# Shuttler_AMC.net
KiCad netlist of a schematic drawn in Altium Designer
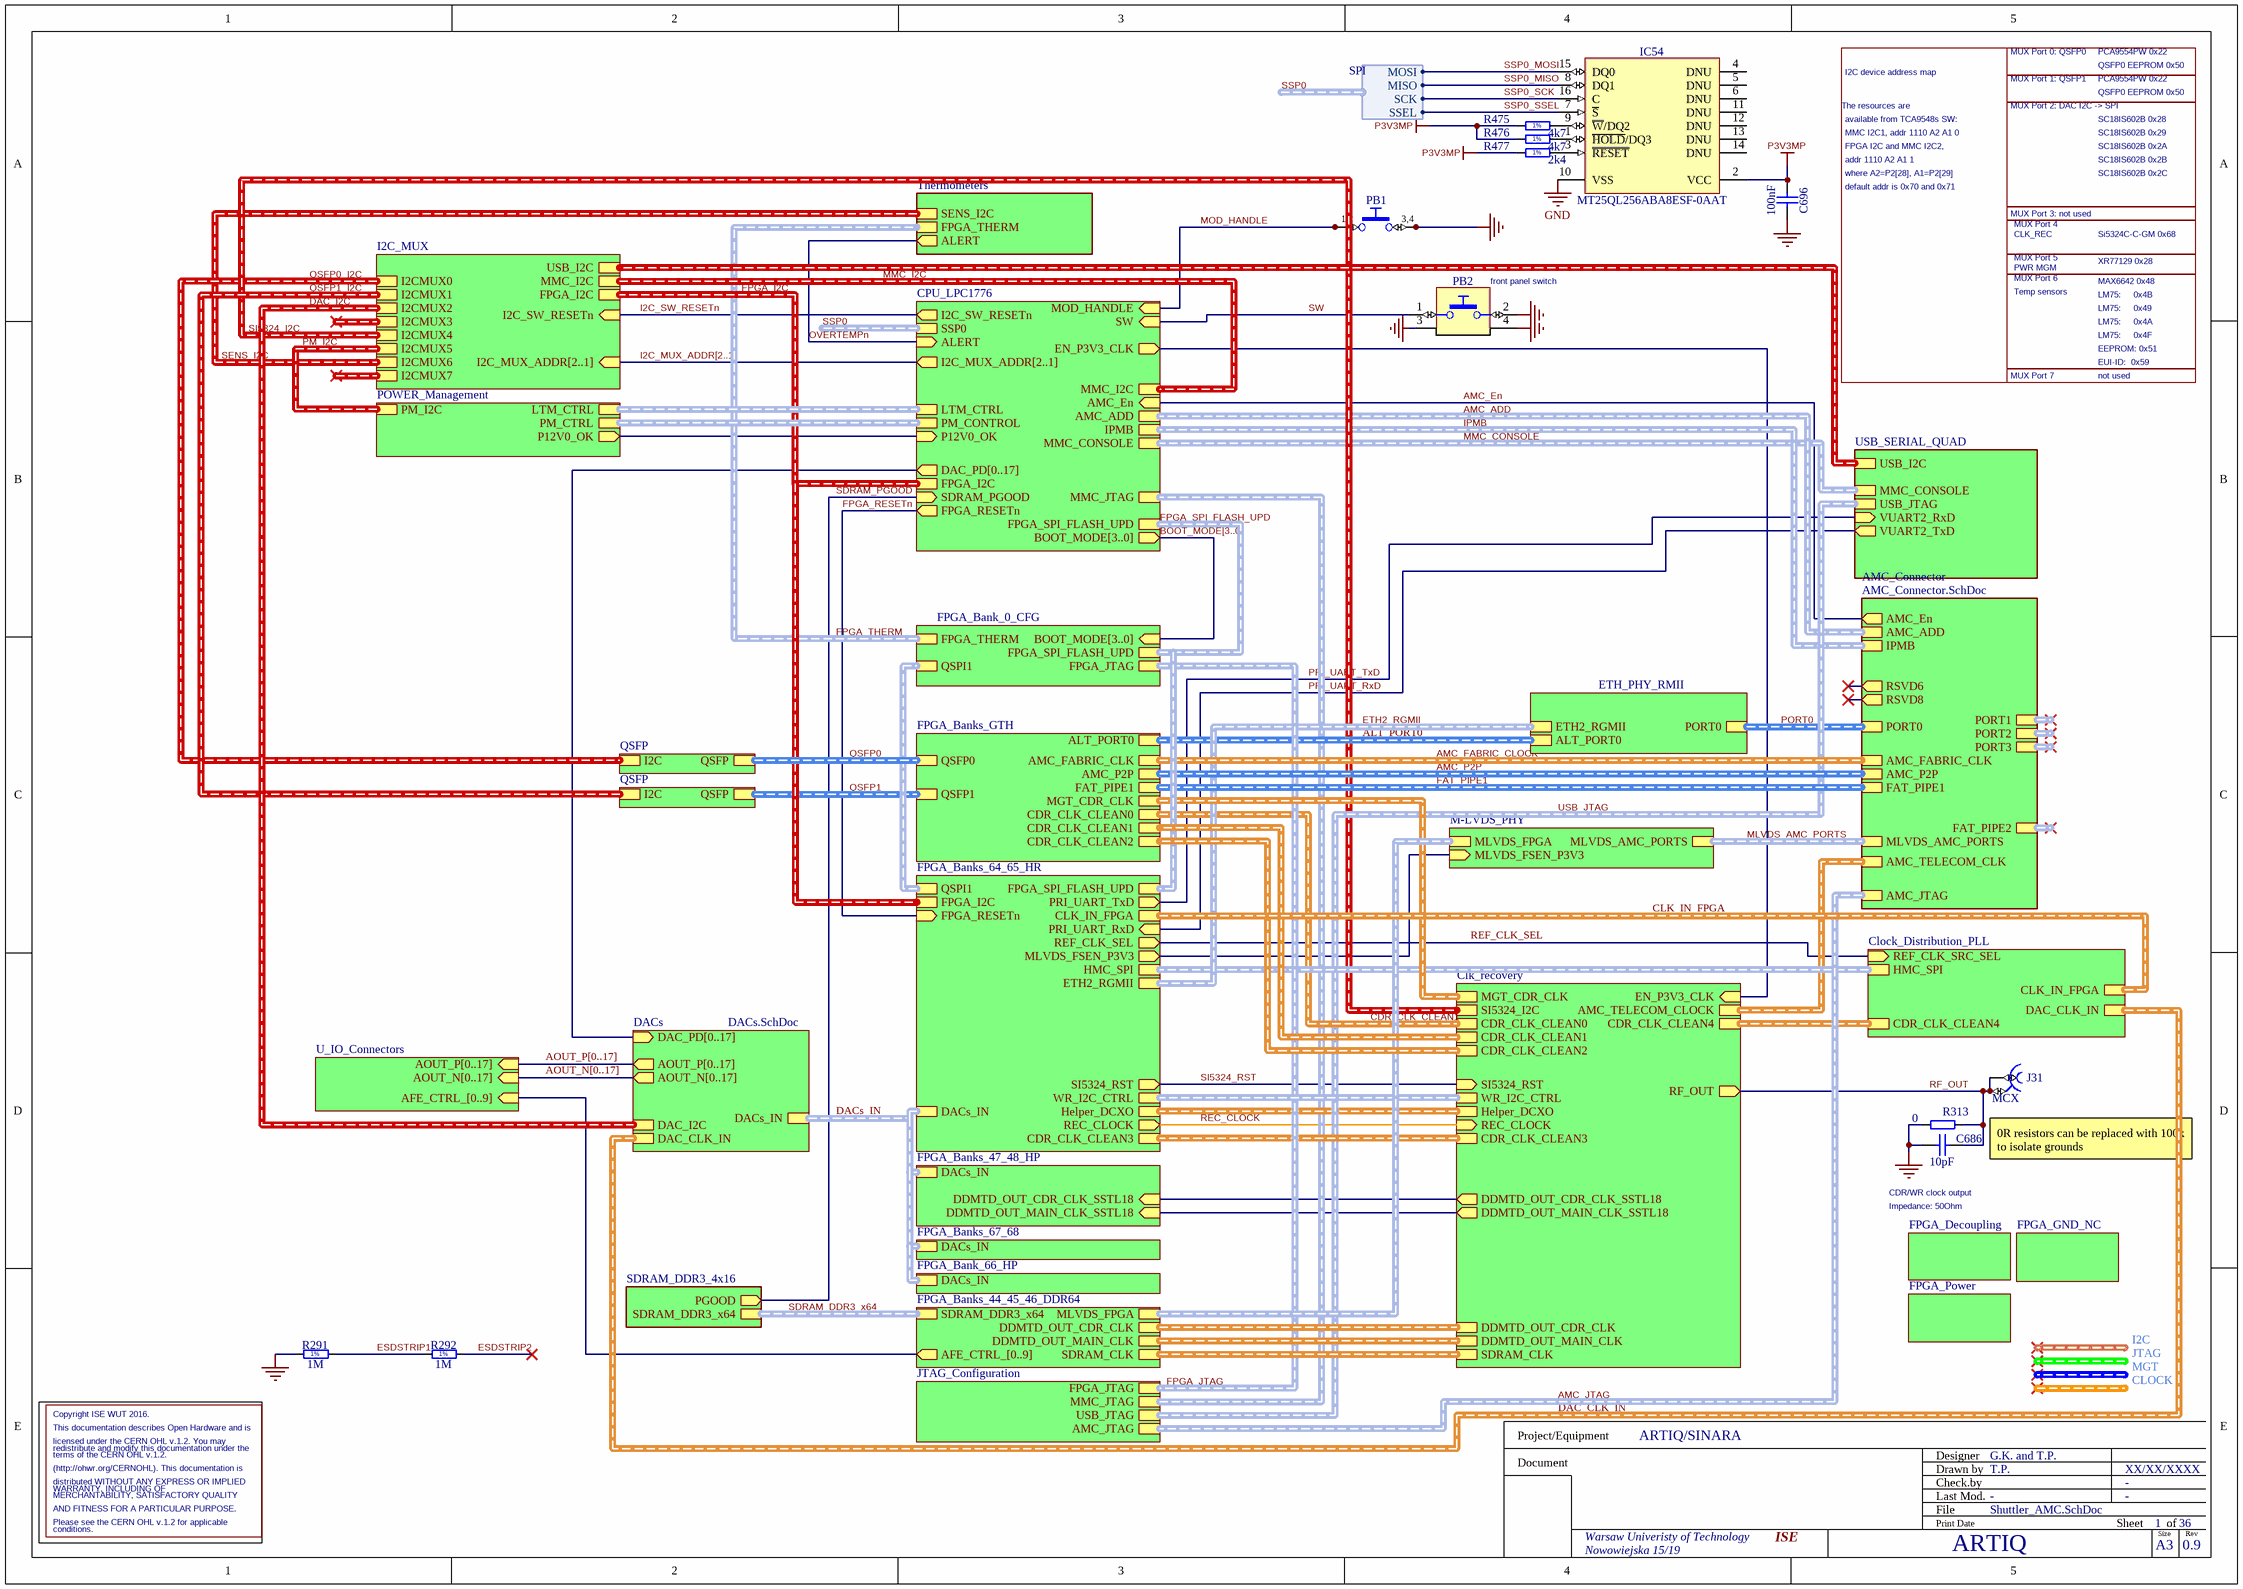
[diagram p0: Shuttler_AMC.SchDoc]

(export (version "E")
  (design (tool "Eeschema 10.0.6"))
  (components
    (comp (ref "C686")
      (value "10pF")
      (footprint "CAPC1608X87N")
      (description "Non-polarised capacitor")
      (fields
        (field (name "MANUFACTURER PART NUMBER") "CC0603_10PF_50V_5%_NP0")
        (field (name "MANUFACTURER") "GENERIC")
        (field (name "AUTHOR") "CERN DEM JLC")
      )
      (libsource (lib "Capacitors") (part "Capacitor - non polarized"))
    )
    (comp (ref "C696")
      (value "100nF")
      (footprint "CAPC0603X33N")
      (description "Non-polarised capacitor")
      (fields
        (field (name "MANUFACTURER PART NUMBER") "CC0201_100NF_6.3V_10%_X5R")
        (field (name "MANUFACTURER") "GENERIC")
        (field (name "AUTHOR") "CERN DEM JLC")
      )
      (libsource (lib "Capacitors") (part "Capacitor - non polarized"))
    )
    (comp (ref "IC54")
      (value "MT25QL256ABA8ESF-0AAT")
      (footprint "SOIC127P1030X265-16N")
      (description "256Mbit (32MB), 2.7V-3.6V, Multiple I/O Serial NOR Flash Memory,with Reset# & Hold#")
      (fields (field (name "MANUFACTURER") "MICRON TECHNOLOGY") (field (name "AUTHOR") "CERN DEM JLC"))
      (libsource (lib "ICs And Semiconductors") (part "MT25QL256ABA8ESF"))
    )
    (comp (ref "J31")
      (value "MCX")
      (footprint "AMPHENOL_ARF2521-ND")
      (fields
        (field (name "PART NUMBER") "AMPHENOL_ARF2521-ND")
        (field (name "MANUFACTURER") "AMPHENOL")
        (field (name "AUTHOR") "GK")
      )
      (libsource (lib "LIBRARY_SCH") (part "CON_MCX"))
    )
    (comp (ref "PB1")
      (value "Push Button")
      (footprint "SW_C&K_HDT0001")
      (description "Push-Button Switch SPDT")
      (fields
        (field (name "MANUFACTURER PART NUMBER") "HDT0001")
        (field (name "MANUFACTURER") "C&K")
        (field (name "AUTHOR") "CERN DEM JLC")
      )
      (libsource (lib "Eletro-mechanical") (part "PB SPST 12NO-34NO"))
    )
    (comp (ref "PB2")
      (value "Push Button")
      (footprint "PB_ALPS_SKHHLQA010")
      (description "Push-Button Switch SPDT")
      (fields
        (field (name "MANUFACTURER PART NUMBER") "SKHHLQA010")
        (field (name "MANUFACTURER") "ALPS")
        (field (name "AUTHOR") "CERN DEM JLC")
      )
      (libsource (lib "Eletro-mechanical") (part "PB SPST 1NO-2NO 34CASE"))
    )
    (comp (ref "R291")
      (value "1M")
      (footprint "RESC5025X65N")
      (description "Resistor - 1%")
      (fields
        (field (name "MANUFACTURER PART NUMBER") "R2010_1M_1%_0.5W_200PPM")
        (field (name "MANUFACTURER") "GENERIC")
        (field (name "AUTHOR") "CERN DEM JLC")
      )
      (libsource (lib "Resistors") (part "Resistor - 1%"))
    )
    (comp (ref "R292")
      (value "1M")
      (footprint "RESC5025X65N")
      (description "Resistor - 1%")
      (fields
        (field (name "MANUFACTURER PART NUMBER") "R2010_1M_1%_0.5W_200PPM")
        (field (name "MANUFACTURER") "GENERIC")
        (field (name "AUTHOR") "CERN DEM JLC")
      )
      (libsource (lib "Resistors") (part "Resistor - 1%"))
    )
    (comp (ref "R313")
      (value "0")
      (footprint "RESC1005X40N")
      (description "Resistor")
      (fields
        (field (name "MANUFACTURER PART NUMBER") "R0402_0R_JUMPER")
        (field (name "MANUFACTURER") "GENERIC")
        (field (name "AUTHOR") "CERN DEM JLC")
      )
      (libsource (lib "Resistors") (part "Resistor"))
    )
    (comp (ref "R475")
      (value "4k7")
      (footprint "RESC1005X40N")
      (description "Resistor - 1%")
      (fields
        (field (name "MANUFACTURER PART NUMBER") "R0402_4K7_1%_0.0625W_100PPM")
        (field (name "MANUFACTURER") "GENERIC")
        (field (name "AUTHOR") "CERN DEM JLC")
      )
      (libsource (lib "Resistors") (part "Resistor - 1%"))
    )
    (comp (ref "R476")
      (value "4k7")
      (footprint "RESC1005X40N")
      (description "Resistor - 1%")
      (fields
        (field (name "MANUFACTURER PART NUMBER") "R0402_4K7_1%_0.0625W_100PPM")
        (field (name "MANUFACTURER") "GENERIC")
        (field (name "AUTHOR") "CERN DEM JLC")
      )
      (libsource (lib "Resistors") (part "Resistor - 1%"))
    )
    (comp (ref "R477")
      (value "2k4")
      (footprint "RESC1005X40N")
      (description "Resistor - 1%")
      (fields
        (field (name "PART NUMBER") "R0402_2K4_1%_0.0625W_100PPM")
        (field (name "POWER") "0.0625W")
        (field (name "AUTHOR") "CERN DEM JLC")
      )
      (libsource (lib "Resistors") (part "Resistor - 1%"))
    )
  )
  (nets
    (net (code "91") (name "/ESDSTRIP1") (class "Default")
      (node (ref "R291") (pin "2") (pinfunction "2_2") (pintype "passive"))
      (node (ref "R292") (pin "1") (pinfunction "1_1") (pintype "passive"))
    )
    (net (code "92") (name "/ESDSTRIP2") (class "Default")
      (node (ref "R292") (pin "2") (pinfunction "2_2") (pintype "passive+no_connect"))
    )
    (net (code "106") (name "/MOD_HANDLE") (class "Default")
      (node (ref "PB1") (pin "1") (pinfunction "1_1") (pintype "bidirectional"))
      (node (ref "PB1") (pin "2") (pinfunction "2_2") (pintype "bidirectional"))
    )
    (net (code "118") (name "/RF_OUT") (class "Default")
      (node (ref "C686") (pin "2") (pinfunction "2_2") (pintype "passive"))
      (node (ref "J31") (pin "1") (pinfunction "1_1") (pintype "bidirectional"))
      (node (ref "J31") (pin "2") (pinfunction "2_2") (pintype "bidirectional"))
      (node (ref "R313") (pin "1") (pinfunction "1_1") (pintype "passive"))
    )
    (net (code "124") (name "/SSP0_MISO") (class "Default")
      (node (ref "IC54") (pin "8") (pinfunction "DQ1_8") (pintype "bidirectional"))
    )
    (net (code "125") (name "/SSP0_MOSI") (class "Default")
      (node (ref "IC54") (pin "15") (pinfunction "DQ0_15") (pintype "bidirectional"))
    )
    (net (code "126") (name "/SSP0_SCK") (class "Default")
      (node (ref "IC54") (pin "16") (pinfunction "C_16") (pintype "input"))
    )
    (net (code "127") (name "/SSP0_SSEL") (class "Default")
      (node (ref "IC54") (pin "7") (pinfunction "~{S}_7") (pintype "input"))
    )
    (net (code "129") (name "/SW") (class "Default")
      (node (ref "PB2") (pin "1") (pinfunction "1_1") (pintype "bidirectional"))
    )
    (net (code "163") (name "GND") (class "Default")
      (node (ref "C686") (pin "1") (pinfunction "1_1") (pintype "passive"))
      (node (ref "C696") (pin "1") (pinfunction "1_1") (pintype "passive"))
      (node (ref "IC54") (pin "10") (pinfunction "VSS_10") (pintype "power_in"))
      (node (ref "PB1") (pin "3") (pinfunction "3_3") (pintype "bidirectional"))
      (node (ref "PB1") (pin "4") (pinfunction "4_4") (pintype "bidirectional"))
      (node (ref "PB2") (pin "2") (pinfunction "2_2") (pintype "bidirectional"))
      (node (ref "PB2") (pin "3") (pinfunction "3_3") (pintype "passive"))
      (node (ref "PB2") (pin "4") (pinfunction "4_4") (pintype "passive"))
      (node (ref "R291") (pin "1") (pinfunction "1_1") (pintype "passive"))
      (node (ref "R313") (pin "2") (pinfunction "2_2") (pintype "passive"))
    )
    (net (code "164") (name "Net-(IC54-~{HOLD}{slash}DQ3)") (class "Default")
      (node (ref "IC54") (pin "1") (pinfunction "~{HOLD}/DQ3_1") (pintype "bidirectional"))
      (node (ref "R476") (pin "2") (pinfunction "2_2") (pintype "passive"))
    )
    (net (code "165") (name "Net-(IC54-~{RESET})") (class "Default")
      (node (ref "IC54") (pin "3") (pinfunction "~{RESET}_3") (pintype "input"))
      (node (ref "R477") (pin "2") (pinfunction "2_2") (pintype "passive"))
    )
    (net (code "166") (name "Net-(IC54-~{W}{slash}DQ2)") (class "Default")
      (node (ref "IC54") (pin "9") (pinfunction "~{W}/DQ2_9") (pintype "bidirectional"))
      (node (ref "R475") (pin "2") (pinfunction "2_2") (pintype "passive"))
    )
    (net (code "167") (name "P3V3MP") (class "Default")
      (node (ref "C696") (pin "2") (pinfunction "2_2") (pintype "passive"))
      (node (ref "IC54") (pin "2") (pinfunction "VCC_2") (pintype "power_in"))
      (node (ref "R475") (pin "1") (pinfunction "1_1") (pintype "passive"))
      (node (ref "R476") (pin "1") (pinfunction "1_1") (pintype "passive"))
      (node (ref "R477") (pin "1") (pinfunction "1_1") (pintype "passive"))
    )
    (net (code "168") (name "unconnected-(IC54-DNU-Pad4)") (class "Default")
      (node (ref "IC54") (pin "4") (pinfunction "DNU_4") (pintype "passive"))
    )
    (net (code "169") (name "unconnected-(IC54-DNU-Pad5)") (class "Default")
      (node (ref "IC54") (pin "5") (pinfunction "DNU_5") (pintype "passive"))
    )
    (net (code "170") (name "unconnected-(IC54-DNU-Pad6)") (class "Default")
      (node (ref "IC54") (pin "6") (pinfunction "DNU_6") (pintype "passive"))
    )
    (net (code "171") (name "unconnected-(IC54-DNU-Pad11)") (class "Default")
      (node (ref "IC54") (pin "11") (pinfunction "DNU_11") (pintype "passive"))
    )
    (net (code "172") (name "unconnected-(IC54-DNU-Pad12)") (class "Default")
      (node (ref "IC54") (pin "12") (pinfunction "DNU_12") (pintype "passive"))
    )
    (net (code "173") (name "unconnected-(IC54-DNU-Pad13)") (class "Default")
      (node (ref "IC54") (pin "13") (pinfunction "DNU_13") (pintype "passive"))
    )
    (net (code "174") (name "unconnected-(IC54-DNU-Pad14)") (class "Default")
      (node (ref "IC54") (pin "14") (pinfunction "DNU_14") (pintype "passive"))
    )
  )
)
